# rw-directish-17mm-mk-2_0.net
KiCad netlist of a schematic drawn in EAGLE
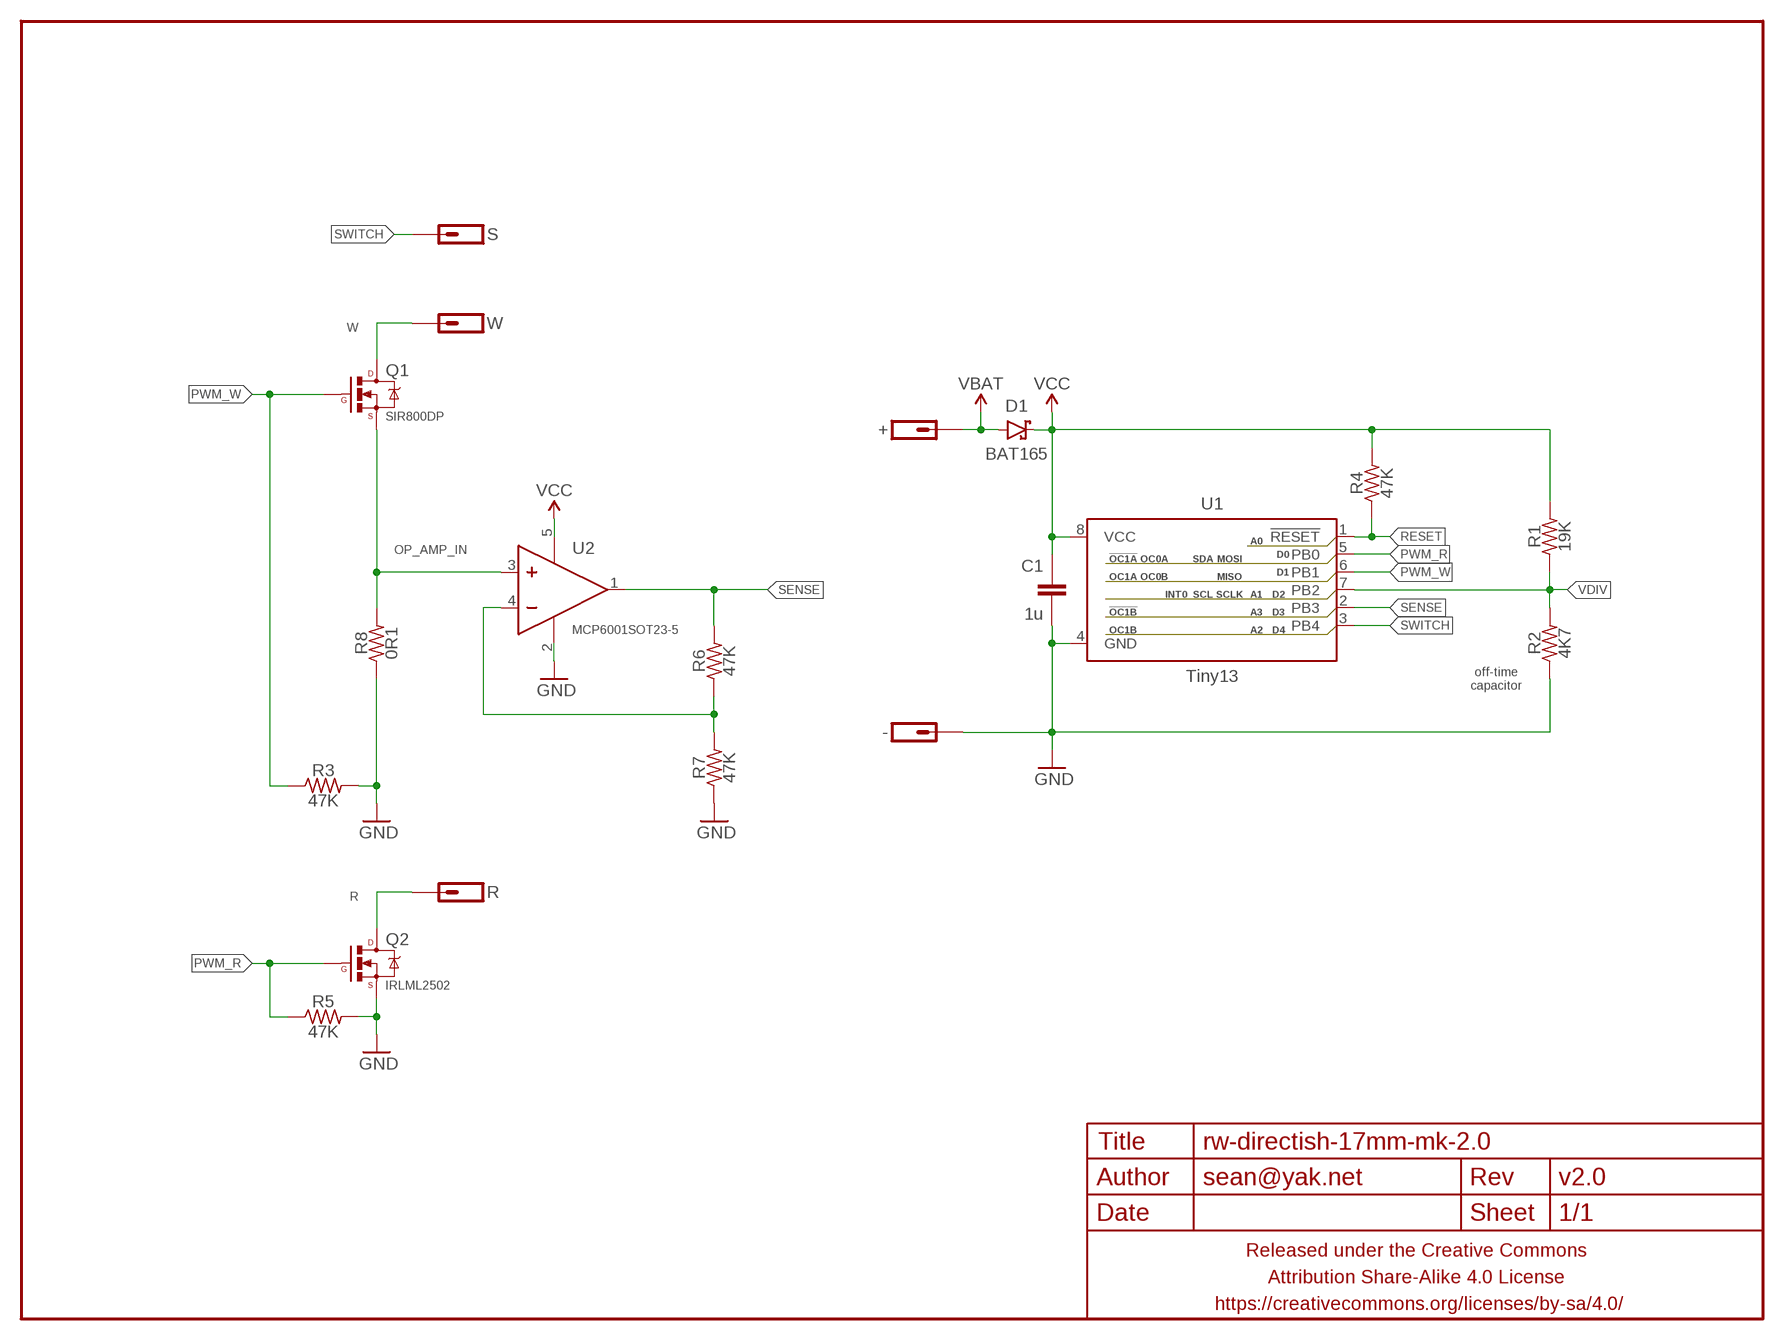
[diagram p0: schematic, sheet 1]

(export (version "E")
  (design (tool "Eeschema 10.0.6"))
  (components
    (comp (ref "+")
      (value "M01PTH-1MM-CIR-NS")
      (footprint "eagle-import:1X01-1MM-CIR-NS")
      (libsource (lib "eagle-import") (part "M01PTH-1MM-CIR-NS"))
    )
    (comp (ref "-")
      (value "M01NOT-A-VIA-NOPE")
      (footprint "eagle-import:1X01_NOSILK_NOSTOP")
      (libsource (lib "eagle-import") (part "M01NOT-A-VIA-NOPE"))
    )
    (comp (ref "C1")
      (value "1u")
      (footprint "eagle-import:C0402")
      (libsource (lib "eagle-import") (part "CAPACITOR-CERAMICC0402"))
    )
    (comp (ref "D1")
      (value "BAT165")
      (footprint "eagle-import:SOD323-SCHOTTKY")
      (libsource (lib "eagle-import") (part "DIODE-SCHOTTKYSOD323"))
    )
    (comp (ref "FRAME1")
      (value "FRAME-LETTERNO_PACKAGE")
      (footprint "eagle-import:DUMMY")
      (fields (field (name "DESIGNER") "sean@yak.net") (field (name "VERSION") "v2.0"))
      (libsource (lib "eagle-import") (part "FRAME-LETTERNO_PACKAGE"))
    )
    (comp (ref "Q1")
      (value "SIR800DP")
      (footprint "eagle-import:POWERPACK-SO-8")
      (libsource (lib "eagle-import") (part "MOSFET-NCHANNELSIR800DP"))
    )
    (comp (ref "Q2")
      (value "IRLML2502")
      (footprint "eagle-import:SOT23-CLOSER")
      (libsource (lib "eagle-import") (part "MOSFET-NCHANNELIRLML2502-SMOL"))
    )
    (comp (ref "R")
      (value "M01SMD-1.25MM-DIA")
      (footprint "eagle-import:1X01-SMD-1.25MM-DIA-NS")
      (libsource (lib "eagle-import") (part "M01SMD-1.25MM-DIA"))
    )
    (comp (ref "R1")
      (value "19K")
      (footprint "eagle-import:R0402")
      (libsource (lib "eagle-import") (part "RESISTORR0402"))
    )
    (comp (ref "R2")
      (value "4K7")
      (footprint "eagle-import:R0402")
      (libsource (lib "eagle-import") (part "RESISTORR0402"))
    )
    (comp (ref "R3")
      (value "47K")
      (footprint "eagle-import:R0402")
      (libsource (lib "eagle-import") (part "RESISTORR0402"))
    )
    (comp (ref "R4")
      (value "47K")
      (footprint "eagle-import:R0402")
      (libsource (lib "eagle-import") (part "RESISTORR0402"))
    )
    (comp (ref "R5")
      (value "47K")
      (footprint "eagle-import:R0402")
      (libsource (lib "eagle-import") (part "RESISTORR0402"))
    )
    (comp (ref "R6")
      (value "47K")
      (footprint "eagle-import:R0402")
      (libsource (lib "eagle-import") (part "RESISTORR0402"))
    )
    (comp (ref "R7")
      (value "47K")
      (footprint "eagle-import:R0402")
      (libsource (lib "eagle-import") (part "RESISTORR0402"))
    )
    (comp (ref "R8")
      (value "0R1")
      (footprint "eagle-import:R0805")
      (libsource (lib "eagle-import") (part "RESISTORR0805"))
    )
    (comp (ref "S")
      (value "M01SMD-1.25MM-DIA")
      (footprint "eagle-import:1X01-SMD-1.25MM-DIA-NS")
      (libsource (lib "eagle-import") (part "M01SMD-1.25MM-DIA"))
    )
    (comp (ref "U1")
      (value "Tiny13")
      (footprint "eagle-import:SO08-NARROWER")
      (libsource (lib "eagle-import") (part "ATTINY13SOIC-NARROWPADS"))
    )
    (comp (ref "U2")
      (value "MCP6001SOT23-5")
      (footprint "eagle-import:SOT23-5")
      (libsource (lib "eagle-import") (part "MCP6001SOT23-5"))
    )
    (comp (ref "W")
      (value "M01SMD-1.25MM-DIA")
      (footprint "eagle-import:1X01-SMD-1.25MM-DIA-NS")
      (libsource (lib "eagle-import") (part "M01SMD-1.25MM-DIA"))
    )
  )
  (nets
    (net (code "1") (name "/OP_AMP_IN") (class "Default")
      (node (ref "Q1") (pin "1") (pinfunction "S_1") (pintype "passive"))
      (node (ref "Q1") (pin "2") (pinfunction "S_2") (pintype "passive"))
      (node (ref "Q1") (pin "3") (pinfunction "S_3") (pintype "passive"))
      (node (ref "R8") (pin "2") (pinfunction "2_2") (pintype "passive"))
      (node (ref "U2") (pin "3") (pinfunction "IN+_3") (pintype "input"))
    )
    (net (code "2") (name "/R") (class "Default")
      (node (ref "Q2") (pin "3") (pinfunction "D_3") (pintype "passive"))
      (node (ref "R") (pin "P$1") (pinfunction "1_P$1") (pintype "passive"))
    )
    (net (code "3") (name "/W") (class "Default")
      (node (ref "Q1") (pin "5678") (pinfunction "D_5678") (pintype "passive"))
      (node (ref "W") (pin "P$1") (pinfunction "1_P$1") (pintype "passive"))
    )
    (net (code "4") (name "GND") (class "Default")
      (node (ref "-") (pin "P$1") (pinfunction "1_P$1") (pintype "passive"))
      (node (ref "C1") (pin "2") (pinfunction "2_2") (pintype "passive"))
      (node (ref "Q2") (pin "2") (pinfunction "S_2") (pintype "passive"))
      (node (ref "R2") (pin "1") (pinfunction "1_1") (pintype "passive"))
      (node (ref "R3") (pin "2") (pinfunction "2_2") (pintype "passive"))
      (node (ref "R5") (pin "2") (pinfunction "2_2") (pintype "passive"))
      (node (ref "R7") (pin "1") (pinfunction "1_1") (pintype "passive"))
      (node (ref "R8") (pin "1") (pinfunction "1_1") (pintype "passive"))
      (node (ref "U1") (pin "4") (pinfunction "GND_4") (pintype "bidirectional"))
      (node (ref "U2") (pin "2") (pinfunction "V-_2") (pintype "power_in"))
    )
    (net (code "5") (name "Net-(U2-IN-)") (class "Default")
      (node (ref "R6") (pin "1") (pinfunction "1_1") (pintype "passive"))
      (node (ref "R7") (pin "2") (pinfunction "2_2") (pintype "passive"))
      (node (ref "U2") (pin "4") (pinfunction "IN-_4") (pintype "input"))
    )
    (net (code "6") (name "PWM_R") (class "Default")
      (node (ref "Q2") (pin "1") (pinfunction "G_1") (pintype "passive"))
      (node (ref "R5") (pin "1") (pinfunction "1_1") (pintype "passive"))
      (node (ref "U1") (pin "5") (pinfunction "PB0_5") (pintype "bidirectional"))
    )
    (net (code "7") (name "PWM_W") (class "Default")
      (node (ref "Q1") (pin "4") (pinfunction "G_4") (pintype "passive"))
      (node (ref "R3") (pin "1") (pinfunction "1_1") (pintype "passive"))
      (node (ref "U1") (pin "6") (pinfunction "PB1_6") (pintype "bidirectional"))
    )
    (net (code "8") (name "RESET") (class "Default")
      (node (ref "R4") (pin "1") (pinfunction "1_1") (pintype "passive"))
      (node (ref "U1") (pin "1") (pinfunction "~{RESET}_1") (pintype "bidirectional"))
    )
    (net (code "9") (name "SENSE") (class "Default")
      (node (ref "R6") (pin "2") (pinfunction "2_2") (pintype "passive"))
      (node (ref "U1") (pin "2") (pinfunction "PB3_2") (pintype "bidirectional"))
      (node (ref "U2") (pin "1") (pinfunction "OUT_1") (pintype "output"))
    )
    (net (code "10") (name "SWITCH") (class "Default")
      (node (ref "S") (pin "P$1") (pinfunction "1_P$1") (pintype "passive"))
      (node (ref "U1") (pin "3") (pinfunction "PB4_3") (pintype "bidirectional"))
    )
    (net (code "11") (name "VBAT") (class "Default")
      (node (ref "+") (pin "1") (pinfunction "1_1") (pintype "passive"))
      (node (ref "D1") (pin "A") (pinfunction "A_A") (pintype "passive"))
    )
    (net (code "12") (name "VCC") (class "Default")
      (node (ref "C1") (pin "1") (pinfunction "1_1") (pintype "passive"))
      (node (ref "D1") (pin "C") (pinfunction "C_C") (pintype "passive"))
      (node (ref "R1") (pin "2") (pinfunction "2_2") (pintype "passive"))
      (node (ref "R4") (pin "2") (pinfunction "2_2") (pintype "passive"))
      (node (ref "U1") (pin "8") (pinfunction "VCC_8") (pintype "bidirectional"))
      (node (ref "U2") (pin "5") (pinfunction "V+_5") (pintype "power_in"))
    )
    (net (code "13") (name "VDIV") (class "Default")
      (node (ref "R1") (pin "1") (pinfunction "1_1") (pintype "passive"))
      (node (ref "R2") (pin "2") (pinfunction "2_2") (pintype "passive"))
      (node (ref "U1") (pin "7") (pinfunction "PB2_7") (pintype "bidirectional"))
    )
  )
)
